# Protection_Circuit_24V.net
KiCad netlist of a schematic drawn in Altium Designer
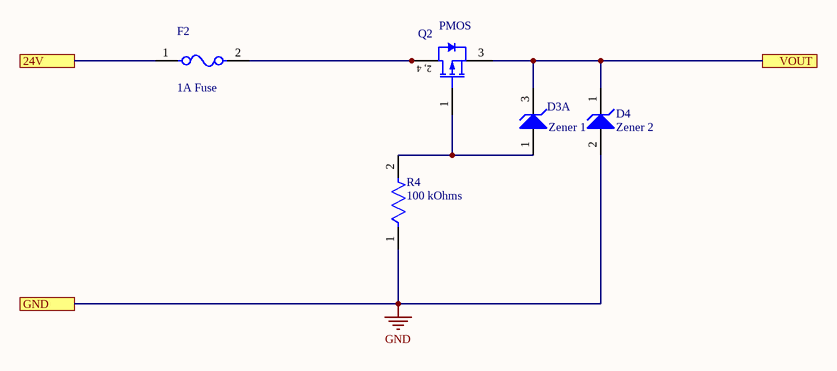
[diagram p0: Protection Circuit 24V.SchDoc]

(export (version "E")
  (design (tool "Eeschema 10.0.6"))
  (components
    (comp (ref "D3")
      (value "Zener 1")
      (footprint "ONSC-SOT-23-3-318-08_V")
      (description "Zener Voltage Regulator, 225 mW, 3-Pin SOT-23, Pb-Free, Tape and Reel")
      (fields (field (name "PARTNUMBER") "MMBZ5245BLT3G") (field (name "MANUFACTURER") "On Semiconductor"))
      (libsource (lib "Altium Content Vault") (part "ONSC-A1K3-3"))
    )
    (comp (ref "D4")
      (value "Zener 2")
      (footprint "ONSC-SMB-2-403A-03_H_V")
      (description "3 W Zener Voltage Regulator, 2-Pin SMB, Pb-Free, Tape and Reel")
      (fields (field (name "MANUFACTURER") "On Semiconductor") (field (name "PARTNUMBER") "1SMB5934BT3G"))
      (libsource (lib "Altium Content Vault") (part "ONSC-K1A2-2"))
    )
    (comp (ref "F2")
      (value "1A Fuse")
      (footprint "FP-0603SFS-MFG")
      (description "FUSE BOARD MOUNT 1A 32VDC 0603")
      (fields
        (field (name "OCTOPART") "https://octopart.com/0603sfs100f%2F32-2-littelfuse-74214378")
        (field (name "MANUFACTURER PART NUMBER") "0603SFS100F/32-2")
      )
      (libsource (lib "Altium Content Vault") (part "5bcf9b9f640e542cf0359d10258e979"))
    )
    (comp (ref "Q2")
      (value "PMOS")
      (footprint "FAIR-SOT223-4_V")
      (fields (field (name "MANUFACTURER") "Fairchild Semiconductor"))
      (libsource (lib "Altium Content Vault") (part "PEMOS-GDSD-4"))
    )
    (comp (ref "R4")
      (value "100 kOhms")
      (footprint "FP-CR0805-MFG")
      (description "Thick Film Chip Resistors 0805 100kΩ 0.125W 5% 200ppm/°C")
      (fields (field (name "TOLERANCE") "5%"))
      (libsource (lib "Altium Content Vault") (part "1029c3af85768c4190bb7ad29bc67b5"))
    )
  )
  (nets
    (net (code "1") (name "/24V") (class "Default")
      (node (ref "F2") (pin "1") (pinfunction "1_1") (pintype "passive"))
    )
    (net (code "2") (name "/VOUT") (class "Default")
      (node (ref "D3") (pin "3") (pinfunction "K_3") (pintype "passive"))
      (node (ref "D4") (pin "1") (pinfunction "K_1") (pintype "passive"))
      (node (ref "Q2") (pin "3") (pinfunction "SOURCE_3") (pintype "passive"))
    )
    (net (code "3") (name "GND") (class "Default")
      (node (ref "D4") (pin "2") (pinfunction "A_2") (pintype "passive"))
      (node (ref "R4") (pin "1") (pinfunction "1_1") (pintype "passive"))
    )
    (net (code "4") (name "Net-(D3A-A)") (class "Default")
      (node (ref "D3") (pin "1") (pinfunction "A_1") (pintype "passive"))
      (node (ref "Q2") (pin "1") (pinfunction "GATE_1") (pintype "passive"))
      (node (ref "R4") (pin "2") (pinfunction "2_2") (pintype "passive"))
    )
    (net (code "5") (name "Net-(F2-Pad2)") (class "Default")
      (node (ref "F2") (pin "2") (pinfunction "2_2") (pintype "passive"))
      (node (ref "Q2") (pin "2") (pinfunction "DRAIN_2") (pintype "passive"))
      (node (ref "Q2") (pin "4") (pinfunction "DRAIN_4") (pintype "passive"))
    )
  )
)
